# LEDChaserSchematic.net
KiCad netlist of a schematic drawn in EAGLE
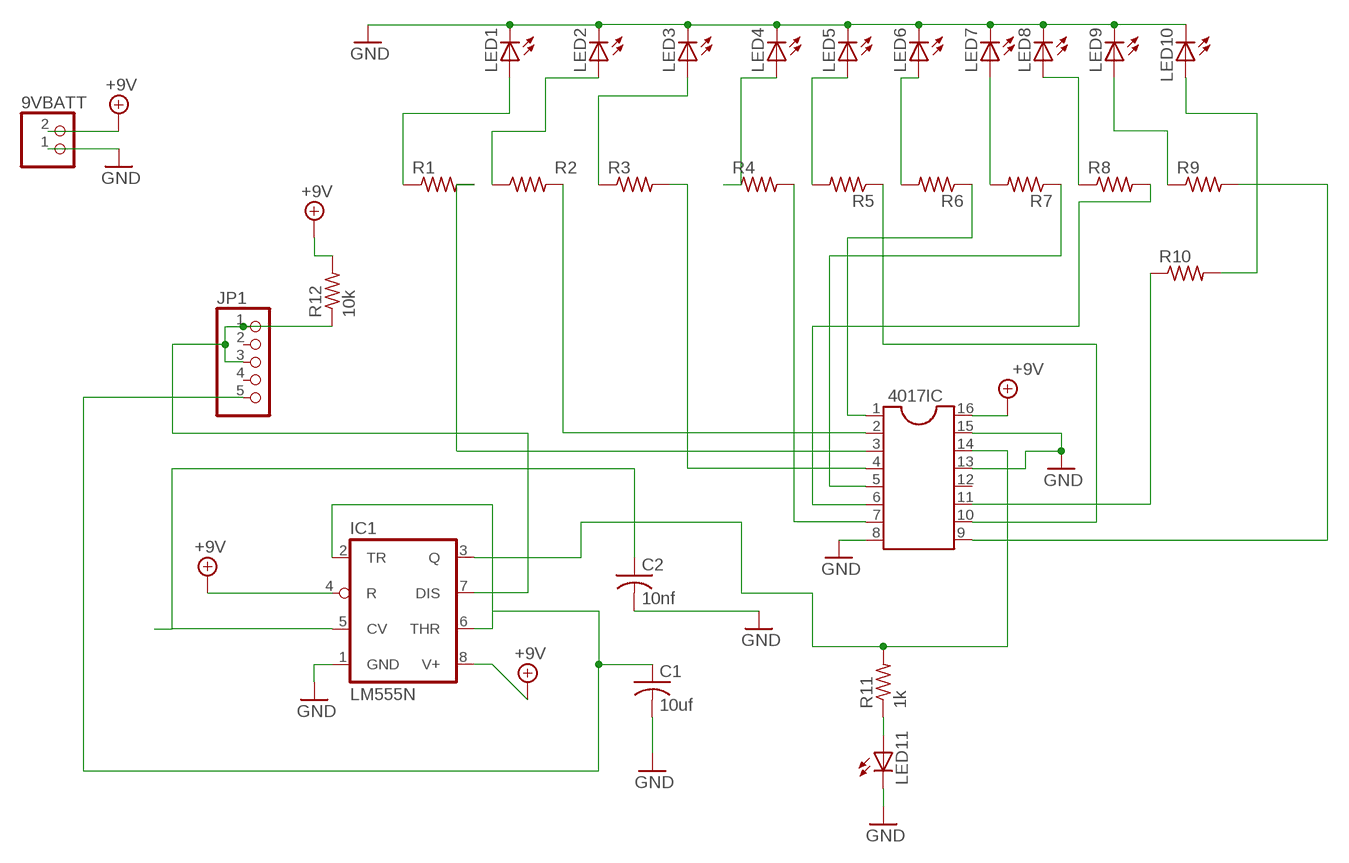
[diagram p0: schematic, sheet 1]

(export (version "E")
  (design (tool "Eeschema 10.0.6"))
  (components
    (comp (ref "9VBATT")
      (value "JST_2PIN-THM")
      (footprint "eagle-import:JST-PH-2-THM")
      (libsource (lib "eagle-import") (part "JST_2PIN-THM"))
    )
    (comp (ref "4017IC")
      (value "DIL16")
      (footprint "eagle-import:DIL16")
      (libsource (lib "eagle-import") (part "DIL16"))
    )
    (comp (ref "C1")
      (value "10uf")
      (footprint "eagle-import:C025-030X050")
      (libsource (lib "eagle-import") (part "C-US025-030X050"))
    )
    (comp (ref "C2")
      (value "10nf")
      (footprint "eagle-import:C025-030X050")
      (libsource (lib "eagle-import") (part "C-US025-030X050"))
    )
    (comp (ref "IC1")
      (value "LM555N")
      (footprint "eagle-import:DIL08-ROUND")
      (libsource (lib "eagle-import") (part "555NLM"))
    )
    (comp (ref "JP1")
      (value "PINHD-1X5")
      (footprint "eagle-import:1X05")
      (libsource (lib "eagle-import") (part "PINHD-1X5"))
    )
    (comp (ref "LED1")
      (value "LED5MM")
      (footprint "eagle-import:LED5MM")
      (libsource (lib "eagle-import") (part "LED5MM"))
    )
    (comp (ref "LED2")
      (value "LED5MM")
      (footprint "eagle-import:LED5MM")
      (libsource (lib "eagle-import") (part "LED5MM"))
    )
    (comp (ref "LED3")
      (value "LED5MM")
      (footprint "eagle-import:LED5MM")
      (libsource (lib "eagle-import") (part "LED5MM"))
    )
    (comp (ref "LED4")
      (value "LED5MM")
      (footprint "eagle-import:LED5MM")
      (libsource (lib "eagle-import") (part "LED5MM"))
    )
    (comp (ref "LED5")
      (value "LED5MM")
      (footprint "eagle-import:LED5MM")
      (libsource (lib "eagle-import") (part "LED5MM"))
    )
    (comp (ref "LED6")
      (value "LED5MM")
      (footprint "eagle-import:LED5MM")
      (libsource (lib "eagle-import") (part "LED5MM"))
    )
    (comp (ref "LED7")
      (value "LED5MM")
      (footprint "eagle-import:LED5MM")
      (libsource (lib "eagle-import") (part "LED5MM"))
    )
    (comp (ref "LED8")
      (value "LED5MM")
      (footprint "eagle-import:LED5MM")
      (libsource (lib "eagle-import") (part "LED5MM"))
    )
    (comp (ref "LED9")
      (value "LED5MM")
      (footprint "eagle-import:LED5MM")
      (libsource (lib "eagle-import") (part "LED5MM"))
    )
    (comp (ref "LED10")
      (value "LED5MM")
      (footprint "eagle-import:LED5MM")
      (libsource (lib "eagle-import") (part "LED5MM"))
    )
    (comp (ref "LED11")
      (value "LED5MM")
      (footprint "eagle-import:LED5MM")
      (libsource (lib "eagle-import") (part "LED5MM"))
    )
    (comp (ref "R1")
      (value "R-US_0204/5")
      (footprint "eagle-import:0204_5")
      (libsource (lib "eagle-import") (part "R-US_0204/5"))
    )
    (comp (ref "R2")
      (value "R-US_0204/5")
      (footprint "eagle-import:0204_5")
      (libsource (lib "eagle-import") (part "R-US_0204/5"))
    )
    (comp (ref "R3")
      (value "R-US_0204/5")
      (footprint "eagle-import:0204_5")
      (libsource (lib "eagle-import") (part "R-US_0204/5"))
    )
    (comp (ref "R4")
      (value "R-US_0204/5")
      (footprint "eagle-import:0204_5")
      (libsource (lib "eagle-import") (part "R-US_0204/5"))
    )
    (comp (ref "R5")
      (value "R-US_0204/5")
      (footprint "eagle-import:0204_5")
      (libsource (lib "eagle-import") (part "R-US_0204/5"))
    )
    (comp (ref "R6")
      (value "R-US_0204/5")
      (footprint "eagle-import:0204_5")
      (libsource (lib "eagle-import") (part "R-US_0204/5"))
    )
    (comp (ref "R7")
      (value "R-US_0204/5")
      (footprint "eagle-import:0204_5")
      (libsource (lib "eagle-import") (part "R-US_0204/5"))
    )
    (comp (ref "R8")
      (value "R-US_0204/5")
      (footprint "eagle-import:0204_5")
      (libsource (lib "eagle-import") (part "R-US_0204/5"))
    )
    (comp (ref "R9")
      (value "R-US_0204/5")
      (footprint "eagle-import:0204_5")
      (libsource (lib "eagle-import") (part "R-US_0204/5"))
    )
    (comp (ref "R10")
      (value "R-US_0204/5")
      (footprint "eagle-import:0204_5")
      (libsource (lib "eagle-import") (part "R-US_0204/5"))
    )
    (comp (ref "R11")
      (value "1k")
      (footprint "eagle-import:0204_5")
      (libsource (lib "eagle-import") (part "R-US_0204/5"))
    )
    (comp (ref "R12")
      (value "10k")
      (footprint "eagle-import:0204_5")
      (libsource (lib "eagle-import") (part "R-US_0204/5"))
    )
  )
  (nets
    (net (code "1") (name "+9V") (class "Default")
      (node (ref "4017IC") (pin "16") (pinfunction "16_16") (pintype "passive"))
      (node (ref "9VBATT") (pin "2") (pinfunction "1_2") (pintype "passive"))
      (node (ref "IC1") (pin "4") (pinfunction "R_4") (pintype "input"))
      (node (ref "IC1") (pin "8") (pinfunction "V+_8") (pintype "power_in"))
      (node (ref "R12") (pin "2") (pinfunction "2_2") (pintype "passive"))
    )
    (net (code "2") (name "GND") (class "Default")
      (node (ref "4017IC") (pin "13") (pinfunction "13_13") (pintype "passive"))
      (node (ref "4017IC") (pin "15") (pinfunction "15_15") (pintype "passive"))
      (node (ref "4017IC") (pin "8") (pinfunction "8_8") (pintype "passive"))
      (node (ref "9VBATT") (pin "1") (pinfunction "2_1") (pintype "passive"))
      (node (ref "C1") (pin "2") (pinfunction "2_2") (pintype "passive"))
      (node (ref "C2") (pin "2") (pinfunction "2_2") (pintype "passive"))
      (node (ref "IC1") (pin "1") (pinfunction "GND_1") (pintype "power_in"))
      (node (ref "LED1") (pin "K") (pinfunction "C_K") (pintype "passive"))
      (node (ref "LED10") (pin "K") (pinfunction "C_K") (pintype "passive"))
      (node (ref "LED11") (pin "K") (pinfunction "C_K") (pintype "passive"))
      (node (ref "LED2") (pin "K") (pinfunction "C_K") (pintype "passive"))
      (node (ref "LED3") (pin "K") (pinfunction "C_K") (pintype "passive"))
      (node (ref "LED4") (pin "K") (pinfunction "C_K") (pintype "passive"))
      (node (ref "LED5") (pin "K") (pinfunction "C_K") (pintype "passive"))
      (node (ref "LED6") (pin "K") (pinfunction "C_K") (pintype "passive"))
      (node (ref "LED7") (pin "K") (pinfunction "C_K") (pintype "passive"))
      (node (ref "LED8") (pin "K") (pinfunction "C_K") (pintype "passive"))
      (node (ref "LED9") (pin "K") (pinfunction "C_K") (pintype "passive"))
    )
    (net (code "3") (name "Net-(4017IC-Pad1)") (class "Default")
      (node (ref "4017IC") (pin "1") (pinfunction "1_1") (pintype "passive"))
      (node (ref "R6") (pin "1") (pinfunction "1_1") (pintype "passive"))
    )
    (net (code "4") (name "Net-(4017IC-Pad2)") (class "Default")
      (node (ref "4017IC") (pin "2") (pinfunction "2_2") (pintype "passive"))
      (node (ref "R2") (pin "2") (pinfunction "2_2") (pintype "passive"))
    )
    (net (code "5") (name "Net-(4017IC-Pad3)") (class "Default")
      (node (ref "4017IC") (pin "3") (pinfunction "3_3") (pintype "passive"))
      (node (ref "R1") (pin "2") (pinfunction "2_2") (pintype "passive"))
    )
    (net (code "6") (name "Net-(4017IC-Pad4)") (class "Default")
      (node (ref "4017IC") (pin "4") (pinfunction "4_4") (pintype "passive"))
      (node (ref "R3") (pin "2") (pinfunction "2_2") (pintype "passive"))
    )
    (net (code "7") (name "Net-(4017IC-Pad5)") (class "Default")
      (node (ref "4017IC") (pin "5") (pinfunction "5_5") (pintype "passive"))
      (node (ref "R7") (pin "1") (pinfunction "1_1") (pintype "passive"))
    )
    (net (code "8") (name "Net-(4017IC-Pad6)") (class "Default")
      (node (ref "4017IC") (pin "6") (pinfunction "6_6") (pintype "passive"))
      (node (ref "R8") (pin "2") (pinfunction "2_2") (pintype "passive"))
    )
    (net (code "9") (name "Net-(4017IC-Pad7)") (class "Default")
      (node (ref "4017IC") (pin "7") (pinfunction "7_7") (pintype "passive"))
      (node (ref "R4") (pin "2") (pinfunction "2_2") (pintype "passive"))
    )
    (net (code "10") (name "Net-(4017IC-Pad9)") (class "Default")
      (node (ref "4017IC") (pin "9") (pinfunction "9_9") (pintype "passive"))
      (node (ref "R9") (pin "2") (pinfunction "2_2") (pintype "passive"))
    )
    (net (code "11") (name "Net-(4017IC-Pad10)") (class "Default")
      (node (ref "4017IC") (pin "10") (pinfunction "10_10") (pintype "passive"))
      (node (ref "R5") (pin "1") (pinfunction "1_1") (pintype "passive"))
    )
    (net (code "12") (name "Net-(4017IC-Pad11)") (class "Default")
      (node (ref "4017IC") (pin "11") (pinfunction "11_11") (pintype "passive"))
      (node (ref "R10") (pin "1") (pinfunction "1_1") (pintype "passive"))
    )
    (net (code "13") (name "Net-(IC1-CV)") (class "Default")
      (node (ref "C2") (pin "1") (pinfunction "1_1") (pintype "passive"))
      (node (ref "IC1") (pin "5") (pinfunction "CV_5") (pintype "input"))
    )
    (net (code "14") (name "Net-(IC1-DIS)") (class "Default")
      (node (ref "IC1") (pin "7") (pinfunction "DIS_7") (pintype "input"))
      (node (ref "JP1") (pin "1") (pinfunction "1_1") (pintype "passive"))
      (node (ref "JP1") (pin "3") (pinfunction "3_3") (pintype "passive"))
      (node (ref "R12") (pin "1") (pinfunction "1_1") (pintype "passive"))
    )
    (net (code "15") (name "Net-(IC1-Q)") (class "Default")
      (node (ref "4017IC") (pin "14") (pinfunction "14_14") (pintype "passive"))
      (node (ref "IC1") (pin "3") (pinfunction "Q_3") (pintype "output"))
      (node (ref "R11") (pin "2") (pinfunction "2_2") (pintype "passive"))
    )
    (net (code "16") (name "Net-(IC1-THR)") (class "Default")
      (node (ref "C1") (pin "1") (pinfunction "1_1") (pintype "passive"))
      (node (ref "IC1") (pin "2") (pinfunction "TR_2") (pintype "input"))
      (node (ref "IC1") (pin "6") (pinfunction "THR_6") (pintype "input"))
      (node (ref "JP1") (pin "5") (pinfunction "5_5") (pintype "passive"))
    )
    (net (code "17") (name "Net-(LED1-PadA)") (class "Default")
      (node (ref "LED1") (pin "A") (pinfunction "A_A") (pintype "passive"))
      (node (ref "R1") (pin "1") (pinfunction "1_1") (pintype "passive"))
    )
    (net (code "18") (name "Net-(LED2-PadA)") (class "Default")
      (node (ref "LED2") (pin "A") (pinfunction "A_A") (pintype "passive"))
      (node (ref "R2") (pin "1") (pinfunction "1_1") (pintype "passive"))
    )
    (net (code "19") (name "Net-(LED3-PadA)") (class "Default")
      (node (ref "LED3") (pin "A") (pinfunction "A_A") (pintype "passive"))
      (node (ref "R3") (pin "1") (pinfunction "1_1") (pintype "passive"))
    )
    (net (code "20") (name "Net-(LED4-PadA)") (class "Default")
      (node (ref "LED4") (pin "A") (pinfunction "A_A") (pintype "passive"))
      (node (ref "R4") (pin "1") (pinfunction "1_1") (pintype "passive"))
    )
    (net (code "21") (name "Net-(LED5-PadA)") (class "Default")
      (node (ref "LED5") (pin "A") (pinfunction "A_A") (pintype "passive"))
      (node (ref "R5") (pin "2") (pinfunction "2_2") (pintype "passive"))
    )
    (net (code "22") (name "Net-(LED6-PadA)") (class "Default")
      (node (ref "LED6") (pin "A") (pinfunction "A_A") (pintype "passive"))
      (node (ref "R6") (pin "2") (pinfunction "2_2") (pintype "passive"))
    )
    (net (code "23") (name "Net-(LED7-PadA)") (class "Default")
      (node (ref "LED7") (pin "A") (pinfunction "A_A") (pintype "passive"))
      (node (ref "R7") (pin "2") (pinfunction "2_2") (pintype "passive"))
    )
    (net (code "24") (name "Net-(LED8-PadA)") (class "Default")
      (node (ref "LED8") (pin "A") (pinfunction "A_A") (pintype "passive"))
      (node (ref "R8") (pin "1") (pinfunction "1_1") (pintype "passive"))
    )
    (net (code "25") (name "Net-(LED9-PadA)") (class "Default")
      (node (ref "LED9") (pin "A") (pinfunction "A_A") (pintype "passive"))
      (node (ref "R9") (pin "1") (pinfunction "1_1") (pintype "passive"))
    )
    (net (code "26") (name "Net-(LED10-PadA)") (class "Default")
      (node (ref "LED10") (pin "A") (pinfunction "A_A") (pintype "passive"))
      (node (ref "R10") (pin "2") (pinfunction "2_2") (pintype "passive"))
    )
    (net (code "27") (name "Net-(LED11-PadA)") (class "Default")
      (node (ref "LED11") (pin "A") (pinfunction "A_A") (pintype "passive"))
      (node (ref "R11") (pin "1") (pinfunction "1_1") (pintype "passive"))
    )
    (net (code "28") (name "unconnected-(4017IC-Pad12)") (class "Default")
      (node (ref "4017IC") (pin "12") (pinfunction "12_12") (pintype "passive"))
    )
    (net (code "29") (name "unconnected-(JP1-Pad2)") (class "Default")
      (node (ref "JP1") (pin "2") (pinfunction "2_2") (pintype "passive"))
    )
    (net (code "30") (name "unconnected-(JP1-Pad4)") (class "Default")
      (node (ref "JP1") (pin "4") (pinfunction "4_4") (pintype "passive"))
    )
  )
)
